# filtro_rev4.net
KiCad netlist of a schematic drawn in Altium Designer
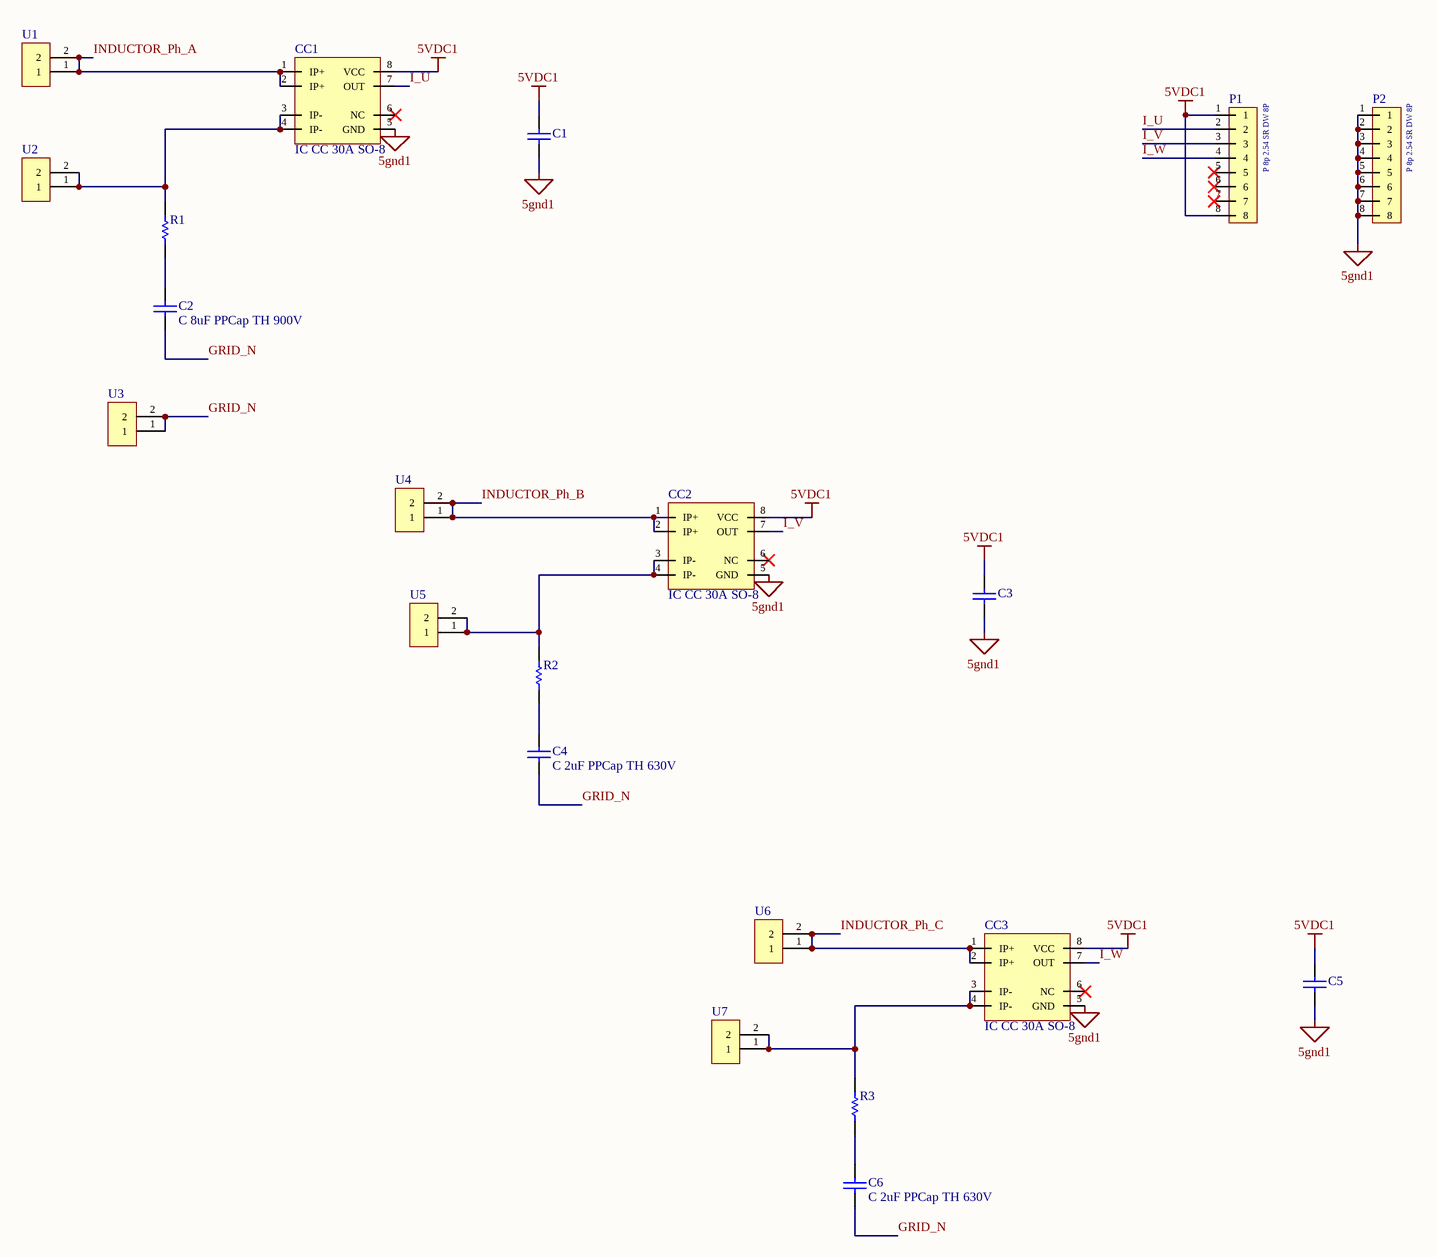
[diagram p0: filtro_rev4.SchDoc]

(export (version "E")
  (design (tool "Eeschema 10.0.6"))
  (components
    (comp (ref "C1")
      (value "C 10uF 0805 MLCC 25V X5R")
      (footprint "CAPC_0805")
      (description "Capacitores de cerâmica multicamada MLCC - SMD/SMT 10uF 25V X5R +/-10% 0805 Gen Purp")
      (fields (field (name "LCSC PART #") "C15850"))
      (libsource (lib "vmorais_libraries") (part "Capacitor SMD"))
    )
    (comp (ref "C2")
      (value "C 8uF PPCap TH 900V")
      (footprint "PWR_CAP_PP_8u")
      (description "Condensador de polipropileno PP KEMET, 8μF, ±5%, 900V dc, Montaje en orificio pasante")
      (libsource (lib "vmorais_libraries") (part "CAPACITOR_dcbus"))
    )
    (comp (ref "C3")
      (value "C 10uF 0805 MLCC 25V X5R")
      (footprint "CAPC_0805")
      (description "Capacitores de cerâmica multicamada MLCC - SMD/SMT 10uF 25V X5R +/-10% 0805 Gen Purp")
      (fields (field (name "LCSC PART #") "C15850"))
      (libsource (lib "vmorais_libraries") (part "Capacitor SMD"))
    )
    (comp (ref "C4")
      (value "C 2uF PPCap TH 630V")
      (footprint "PWR_CAP_PP_8u")
      (description "Capacitores de película 2.0uF 630volts 10% 37.5mmL/S 1.0mmL/D")
      (libsource (lib "vmorais_libraries") (part "CAPACITOR_dcbus"))
    )
    (comp (ref "C5")
      (value "C 10uF 0805 MLCC 25V X5R")
      (footprint "CAPC_0805")
      (description "Capacitores de cerâmica multicamada MLCC - SMD/SMT 10uF 25V X5R +/-10% 0805 Gen Purp")
      (fields (field (name "LCSC PART #") "C15850"))
      (libsource (lib "vmorais_libraries") (part "Capacitor SMD"))
    )
    (comp (ref "C6")
      (value "C 2uF PPCap TH 630V")
      (footprint "PWR_CAP_PP_8u")
      (description "Capacitores de película 2.0uF 630volts 10% 37.5mmL/S 1.0mmL/D")
      (libsource (lib "vmorais_libraries") (part "CAPACITOR_dcbus"))
    )
    (comp (ref "CC1")
      (value "IC CC 30A SO-8")
      (footprint "CC6303_SOP8")
      (description "Sensores de Corrente de Montagem de Painel Hall Effect IC LF 30A 66 mV/A")
      (fields (field (name "LCSC PART #") "C10681"))
      (libsource (lib "vmorais_libraries") (part "Current_Sensor_cc6303"))
    )
    (comp (ref "CC2")
      (value "IC CC 30A SO-8")
      (footprint "CC6303_SOP8")
      (description "Sensores de Corrente de Montagem de Painel Hall Effect IC LF 30A 66 mV/A")
      (fields (field (name "LCSC PART #") "C10681"))
      (libsource (lib "vmorais_libraries") (part "Current_Sensor_cc6303"))
    )
    (comp (ref "CC3")
      (value "IC CC 30A SO-8")
      (footprint "CC6303_SOP8")
      (description "Sensores de Corrente de Montagem de Painel Hall Effect IC LF 30A 66 mV/A")
      (fields (field (name "LCSC PART #") "C10681"))
      (libsource (lib "vmorais_libraries") (part "Current_Sensor_cc6303"))
    )
    (comp (ref "P1")
      (value "P 8p 2.54 SR DW 8P")
      (footprint "Header 8x1 8.5mm")
      (description "Distribuidores e Alojamento de Fios CGrid Hrd SRDW THo le 8ckt")
      (libsource (lib "vmorais_libraries") (part "jumper_8p"))
    )
    (comp (ref "P2")
      (value "P 8p 2.54 SR DW 8P")
      (footprint "Header 8x1 8.5mm")
      (description "Distribuidores e Alojamento de Fios CGrid Hrd SRDW THo le 8ckt")
      (libsource (lib "vmorais_libraries") (part "jumper_8p"))
    )
    (comp (ref "R1")
      (value "R 2.2 3W TH 5%")
      (footprint "PWR_RESC_3W")
      (description "Resistencia TE Connectivity, de 2.2Ω ±5%, 3W, Serie ROX3S")
      (libsource (lib "vmorais_libraries") (part "Resistor"))
    )
    (comp (ref "R2")
      (value "R 2.2 3W TH 5%")
      (footprint "PWR_RESC_3W")
      (description "Resistencia TE Connectivity, de 2.2Ω ±5%, 3W, Serie ROX3S")
      (libsource (lib "vmorais_libraries") (part "Resistor"))
    )
    (comp (ref "R3")
      (value "R 2.2 3W TH 5%")
      (footprint "PWR_RESC_3W")
      (description "Resistencia TE Connectivity, de 2.2Ω ±5%, 3W, Serie ROX3S")
      (libsource (lib "vmorais_libraries") (part "Resistor"))
    )
    (comp (ref "U1")
      (value "P 2p 5mm")
      (footprint "connector1x2_parafuso")
      (description "Bloques de terminales de PCB de perfil estándar RS de 5,0 mm")
      (libsource (lib "vmorais_libraries") (part "gen_purpose_conn_1x2"))
    )
    (comp (ref "U2")
      (value "P 2p 5mm")
      (footprint "connector1x2_parafuso")
      (description "Bloques de terminales de PCB de perfil estándar RS de 5,0 mm")
      (libsource (lib "vmorais_libraries") (part "gen_purpose_conn_1x2"))
    )
    (comp (ref "U3")
      (value "P 2p 5mm")
      (footprint "connector1x2_parafuso")
      (description "Bloques de terminales de PCB de perfil estándar RS de 5,0 mm")
      (libsource (lib "vmorais_libraries") (part "gen_purpose_conn_1x2"))
    )
    (comp (ref "U4")
      (value "P 2p 5mm")
      (footprint "connector1x2_parafuso")
      (description "Bloques de terminales de PCB de perfil estándar RS de 5,0 mm")
      (libsource (lib "vmorais_libraries") (part "gen_purpose_conn_1x2"))
    )
    (comp (ref "U5")
      (value "P 2p 5mm")
      (footprint "connector1x2_parafuso")
      (description "Bloques de terminales de PCB de perfil estándar RS de 5,0 mm")
      (libsource (lib "vmorais_libraries") (part "gen_purpose_conn_1x2"))
    )
    (comp (ref "U6")
      (value "P 2p 5mm")
      (footprint "connector1x2_parafuso")
      (description "Bloques de terminales de PCB de perfil estándar RS de 5,0 mm")
      (libsource (lib "vmorais_libraries") (part "gen_purpose_conn_1x2"))
    )
    (comp (ref "U7")
      (value "P 2p 5mm")
      (footprint "connector1x2_parafuso")
      (description "Bloques de terminales de PCB de perfil estándar RS de 5,0 mm")
      (libsource (lib "vmorais_libraries") (part "gen_purpose_conn_1x2"))
    )
  )
  (nets
    (net (code "1") (name "/GRID_N") (class "Default")
      (node (ref "C2") (pin "1") (pinfunction "1_1") (pintype "passive"))
      (node (ref "C4") (pin "1") (pinfunction "1_1") (pintype "passive"))
      (node (ref "C6") (pin "1") (pinfunction "1_1") (pintype "passive"))
      (node (ref "U3") (pin "1") (pinfunction "1_1") (pintype "passive"))
      (node (ref "U3") (pin "2") (pinfunction "2_2") (pintype "passive"))
    )
    (net (code "2") (name "/INDUCTOR_Ph_A") (class "Default")
      (node (ref "CC1") (pin "1") (pinfunction "IP+_1") (pintype "passive"))
      (node (ref "CC1") (pin "2") (pinfunction "IP+_2") (pintype "passive"))
      (node (ref "U1") (pin "1") (pinfunction "1_1") (pintype "passive"))
      (node (ref "U1") (pin "2") (pinfunction "2_2") (pintype "passive"))
    )
    (net (code "3") (name "/INDUCTOR_Ph_B") (class "Default")
      (node (ref "CC2") (pin "1") (pinfunction "IP+_1") (pintype "passive"))
      (node (ref "CC2") (pin "2") (pinfunction "IP+_2") (pintype "passive"))
      (node (ref "U4") (pin "1") (pinfunction "1_1") (pintype "passive"))
      (node (ref "U4") (pin "2") (pinfunction "2_2") (pintype "passive"))
    )
    (net (code "4") (name "/INDUCTOR_Ph_C") (class "Default")
      (node (ref "CC3") (pin "1") (pinfunction "IP+_1") (pintype "passive"))
      (node (ref "CC3") (pin "2") (pinfunction "IP+_2") (pintype "passive"))
      (node (ref "U6") (pin "1") (pinfunction "1_1") (pintype "passive"))
      (node (ref "U6") (pin "2") (pinfunction "2_2") (pintype "passive"))
    )
    (net (code "5") (name "/I_U") (class "Default")
      (node (ref "CC1") (pin "7") (pinfunction "OUT_7") (pintype "passive"))
      (node (ref "P1") (pin "2") (pinfunction "2_2") (pintype "passive"))
    )
    (net (code "6") (name "/I_V") (class "Default")
      (node (ref "CC2") (pin "7") (pinfunction "OUT_7") (pintype "passive"))
      (node (ref "P1") (pin "3") (pinfunction "3_3") (pintype "passive"))
    )
    (net (code "7") (name "/I_W") (class "Default")
      (node (ref "CC3") (pin "7") (pinfunction "OUT_7") (pintype "passive"))
      (node (ref "P1") (pin "4") (pinfunction "4_4") (pintype "passive"))
    )
    (net (code "8") (name "5VDC1") (class "Default")
      (node (ref "C1") (pin "2") (pinfunction "2_2") (pintype "passive"))
      (node (ref "C3") (pin "2") (pinfunction "2_2") (pintype "passive"))
      (node (ref "C5") (pin "2") (pinfunction "2_2") (pintype "passive"))
      (node (ref "CC1") (pin "8") (pinfunction "VCC_8") (pintype "passive"))
      (node (ref "CC2") (pin "8") (pinfunction "VCC_8") (pintype "passive"))
      (node (ref "CC3") (pin "8") (pinfunction "VCC_8") (pintype "passive"))
      (node (ref "P1") (pin "1") (pinfunction "1_1") (pintype "passive"))
      (node (ref "P1") (pin "8") (pinfunction "8_8") (pintype "passive"))
    )
    (net (code "9") (name "5gnd1") (class "Default")
      (node (ref "C1") (pin "1") (pinfunction "1_1") (pintype "passive"))
      (node (ref "C3") (pin "1") (pinfunction "1_1") (pintype "passive"))
      (node (ref "C5") (pin "1") (pinfunction "1_1") (pintype "passive"))
      (node (ref "CC1") (pin "5") (pinfunction "GND_5") (pintype "passive"))
      (node (ref "CC2") (pin "5") (pinfunction "GND_5") (pintype "passive"))
      (node (ref "CC3") (pin "5") (pinfunction "GND_5") (pintype "passive"))
      (node (ref "P2") (pin "1") (pinfunction "1_1") (pintype "passive"))
      (node (ref "P2") (pin "2") (pinfunction "2_2") (pintype "passive"))
      (node (ref "P2") (pin "3") (pinfunction "3_3") (pintype "passive"))
      (node (ref "P2") (pin "4") (pinfunction "4_4") (pintype "passive"))
      (node (ref "P2") (pin "5") (pinfunction "5_5") (pintype "passive"))
      (node (ref "P2") (pin "6") (pinfunction "6_6") (pintype "passive"))
      (node (ref "P2") (pin "7") (pinfunction "7_7") (pintype "passive"))
      (node (ref "P2") (pin "8") (pinfunction "8_8") (pintype "passive"))
    )
    (net (code "10") (name "Net-(C2-Pad2)") (class "Default")
      (node (ref "C2") (pin "2") (pinfunction "2_2") (pintype "passive"))
      (node (ref "R1") (pin "1") (pinfunction "1_1") (pintype "passive"))
    )
    (net (code "11") (name "Net-(C4-Pad2)") (class "Default")
      (node (ref "C4") (pin "2") (pinfunction "2_2") (pintype "passive"))
      (node (ref "R2") (pin "1") (pinfunction "1_1") (pintype "passive"))
    )
    (net (code "12") (name "Net-(C6-Pad2)") (class "Default")
      (node (ref "C6") (pin "2") (pinfunction "2_2") (pintype "passive"))
      (node (ref "R3") (pin "1") (pinfunction "1_1") (pintype "passive"))
    )
    (net (code "13") (name "Net-(CC1-IP--Pad3)") (class "Default")
      (node (ref "CC1") (pin "3") (pinfunction "IP-_3") (pintype "passive"))
      (node (ref "CC1") (pin "4") (pinfunction "IP-_4") (pintype "passive"))
      (node (ref "R1") (pin "2") (pinfunction "2_2") (pintype "passive"))
      (node (ref "U2") (pin "1") (pinfunction "1_1") (pintype "passive"))
      (node (ref "U2") (pin "2") (pinfunction "2_2") (pintype "passive"))
    )
    (net (code "14") (name "Net-(CC2-IP--Pad3)") (class "Default")
      (node (ref "CC2") (pin "3") (pinfunction "IP-_3") (pintype "passive"))
      (node (ref "CC2") (pin "4") (pinfunction "IP-_4") (pintype "passive"))
      (node (ref "R2") (pin "2") (pinfunction "2_2") (pintype "passive"))
      (node (ref "U5") (pin "1") (pinfunction "1_1") (pintype "passive"))
      (node (ref "U5") (pin "2") (pinfunction "2_2") (pintype "passive"))
    )
    (net (code "15") (name "Net-(CC3-IP--Pad3)") (class "Default")
      (node (ref "CC3") (pin "3") (pinfunction "IP-_3") (pintype "passive"))
      (node (ref "CC3") (pin "4") (pinfunction "IP-_4") (pintype "passive"))
      (node (ref "R3") (pin "2") (pinfunction "2_2") (pintype "passive"))
      (node (ref "U7") (pin "1") (pinfunction "1_1") (pintype "passive"))
      (node (ref "U7") (pin "2") (pinfunction "2_2") (pintype "passive"))
    )
    (net (code "16") (name "unconnected-(CC1-NC-Pad6)") (class "Default")
      (node (ref "CC1") (pin "6") (pinfunction "NC_6") (pintype "passive+no_connect"))
    )
    (net (code "17") (name "unconnected-(CC2-NC-Pad6)") (class "Default")
      (node (ref "CC2") (pin "6") (pinfunction "NC_6") (pintype "passive+no_connect"))
    )
    (net (code "18") (name "unconnected-(CC3-NC-Pad6)") (class "Default")
      (node (ref "CC3") (pin "6") (pinfunction "NC_6") (pintype "passive+no_connect"))
    )
    (net (code "19") (name "unconnected-(P1-Pad5)") (class "Default")
      (node (ref "P1") (pin "5") (pinfunction "5_5") (pintype "passive+no_connect"))
    )
    (net (code "20") (name "unconnected-(P1-Pad6)") (class "Default")
      (node (ref "P1") (pin "6") (pinfunction "6_6") (pintype "passive+no_connect"))
    )
    (net (code "21") (name "unconnected-(P1-Pad7)") (class "Default")
      (node (ref "P1") (pin "7") (pinfunction "7_7") (pintype "passive+no_connect"))
    )
  )
)
